# Adorkable_Base_V2_EXP_V1_1.net
KiCad netlist of a schematic drawn in EasyEDA Pro
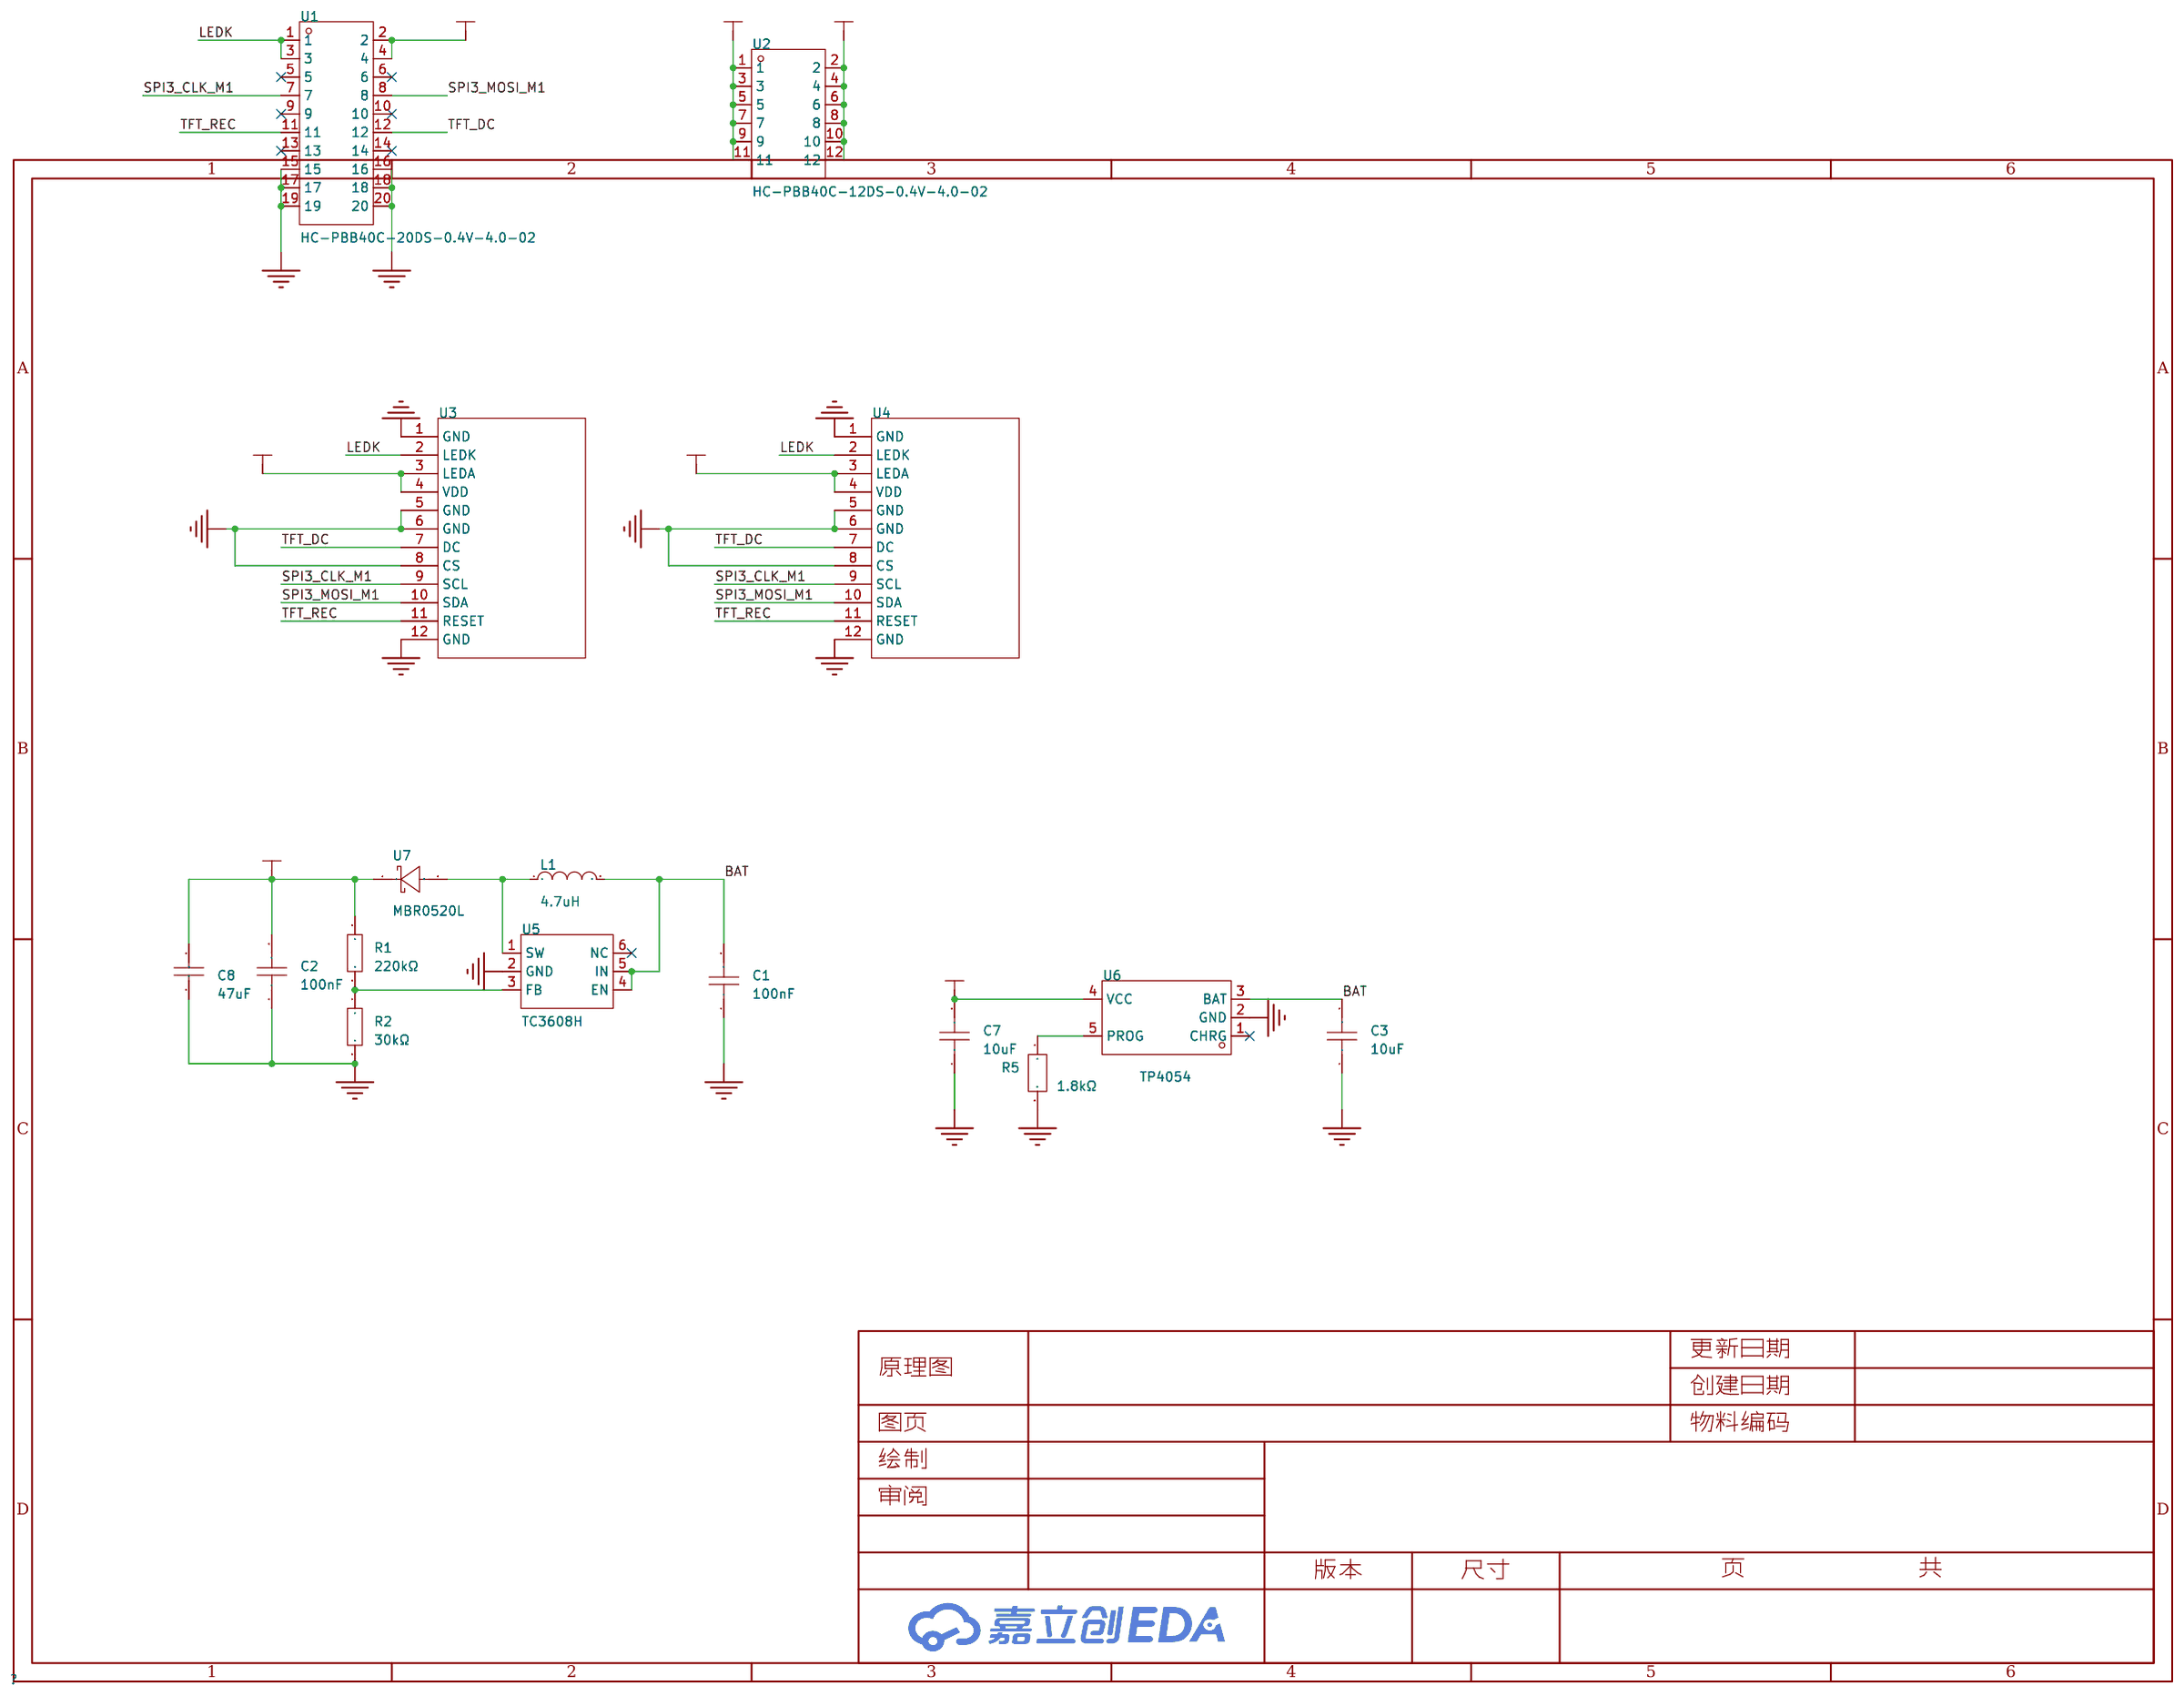
[diagram p0: schematic sheet]

(export (version "E")
  (design (tool "Eeschema 10.0.6"))
  (components
    (comp (ref "C1")
      (value "100nF")
      (footprint "easyedapro:C0603")
      (description "容值:100nF;精度:±10%;额定电压:50V;温度系数:X7R;")
      (fields
        (field (name "Manufacturer Part") "CL10B104KB8NNNC")
        (field (name "Manufacturer") "SAMSUNG(三星)")
      )
      (libsource (lib "easyedapro") (part "CL10B104KB8NNNC"))
    )
    (comp (ref "C2")
      (value "100nF")
      (footprint "easyedapro:C0603")
      (description "容值:100nF;精度:±10%;额定电压:50V;温度系数:X7R;")
      (fields
        (field (name "Manufacturer Part") "CL10B104KB8NNNC")
        (field (name "Manufacturer") "SAMSUNG(三星)")
      )
      (libsource (lib "easyedapro") (part "CL10B104KB8NNNC"))
    )
    (comp (ref "C3")
      (value "10uF")
      (footprint "easyedapro:C0603")
      (description "容值:10uF;精度:±10%;额定电压:10V;温度系数:X5R;")
      (fields
        (field (name "Manufacturer Part") "CL10A106KP8NNNC")
        (field (name "Manufacturer") "SAMSUNG(三星)")
      )
      (libsource (lib "easyedapro") (part "CL10A106KP8NNNC"))
    )
    (comp (ref "C7")
      (value "10uF")
      (footprint "easyedapro:C0603")
      (description "容值:10uF;精度:±10%;额定电压:10V;温度系数:X5R;")
      (fields
        (field (name "Manufacturer Part") "CL10A106KP8NNNC")
        (field (name "Manufacturer") "SAMSUNG(三星)")
      )
      (libsource (lib "easyedapro") (part "CL10A106KP8NNNC"))
    )
    (comp (ref "C8")
      (value "47uF")
      (footprint "easyedapro:C0603")
      (description "容值:47uF;精度:±20%;额定电压:6.3V;材质(温度系数):X5R;")
      (fields
        (field (name "Manufacturer Part") "GRM188R60J476ME15D")
        (field (name "Manufacturer") "muRata(村田)")
      )
      (libsource (lib "easyedapro") (part "GRM188R60J476ME15D"))
    )
    (comp (ref "L1")
      (value "4.7uH")
      (footprint "easyedapro:IND-SMD_L2.5-W2.0-VLS252012CX-150M")
      (description "电感值:4.7uH;精度:±20%;额定电流:2A;饱和电流(Isat):2.6A;类型:一体成型电感;")
      (fields
        (field (name "Manufacturer Part") "FTC252010S4R7MBCA")
        (field (name "Manufacturer") "cjiang(长江微电)")
      )
      (libsource (lib "easyedapro") (part "FTC252010S4R7MBCA"))
    )
    (comp (ref "R1")
      (value "220kΩ")
      (footprint "easyedapro:R0603")
      (description "电阻类型:厚膜电阻;阻值:220kΩ;精度:±1%;功率:100mW;工作电压:75V;温度系数:±100ppm/°C;")
      (fields
        (field (name "Manufacturer Part") "0603WAF2203T5E")
        (field (name "Manufacturer") "UNI-ROYAL(厚声)")
      )
      (libsource (lib "easyedapro") (part "0603WAF2203T5E"))
    )
    (comp (ref "R2")
      (value "30kΩ")
      (footprint "easyedapro:R0603")
      (description "电阻类型:厚膜电阻;阻值:30kΩ;精度:±1%;功率:100mW;工作电压:75V;温度系数:±100ppm/°C;")
      (fields
        (field (name "Manufacturer Part") "0603WAF3002T5E")
        (field (name "Manufacturer") "UNI-ROYAL(厚声)")
      )
      (libsource (lib "easyedapro") (part "0603WAF3002T5E"))
    )
    (comp (ref "R5")
      (value "1.8kΩ")
      (footprint "easyedapro:R0603")
      (description "电阻类型:厚膜电阻;阻值:1.8kΩ;精度:±1%;功率:100mW;工作电压:75V;温度系数:±100ppm/°C;")
      (fields (field (name "Manufacturer Part") "FRC0603F1801TS") (field (name "Manufacturer") "FOJAN(富捷)"))
      (libsource (lib "easyedapro") (part "FRC0603F1801TS"))
    )
    (comp (ref "U1")
      (value "HC-PBB40C-20DS-0.4V-4.0-02")
      (footprint "easyedapro:CONN-SMD_20P-P0.40_DF40C-20DS-0.4V")
      (description "PIN总数:20P;间距:0.4mm;安装方式:立贴;排数:2;额定电流:300mA;工作温度:-40°C~+85°C;")
      (fields (field (name "Manufacturer") "HCTL(华灿天禄)"))
      (libsource (lib "easyedapro") (part "HC-PBB40C-20DS-0.4V-4.0-02"))
    )
    (comp (ref "U2")
      (value "HC-PBB40C-12DS-0.4V-4.0-02")
      (footprint "easyedapro:CONN-SMD_12P-P0.40_HC-PBB40C-12DS-0.4V")
      (description "PIN总数:12P;间距:0.4mm;安装方式:立贴;排数:2;额定电流:300mA;工作温度:-40°C~+85°C;")
      (fields (field (name "Manufacturer") "HCTL(华灿天禄)"))
      (libsource (lib "easyedapro") (part "HC-PBB40C-12DS-0.4V-4.0-02"))
    )
    (comp (ref "U3") (value "~") (footprint "easyedapro:LCD") (libsource (lib "easyedapro") (part "LCD")))
    (comp (ref "U4") (value "~") (footprint "easyedapro:LCD") (libsource (lib "easyedapro") (part "LCD")))
    (comp (ref "U5")
      (value "TC3608H")
      (footprint "easyedapro:SOT-23-6_L2.9-W1.6-P0.95-LS2.8-BR")
      (description "功能类型:升压型;输出类型:-;工作电压:2.3V~15V;输出电压:-;输出电流:-;")
      (fields (field (name "Manufacturer") "FM(富满)"))
      (libsource (lib "easyedapro") (part "TC3608H."))
    )
    (comp (ref "U6")
      (value "TP4054")
      (footprint "easyedapro:TSOT-23-5_L2.9-W1.6-P0.95-LS2.8-BR")
      (description "电源电压:6.5V;最大充电电流:500mA;电池类型:锂离子/聚合物;电池节数:1;")
      (fields (field (name "Manufacturer") "UMW(友台半导体)"))
      (libsource (lib "easyedapro") (part "TP4054_C668215"))
    )
    (comp (ref "U7")
      (value "MBR0520L")
      (footprint "easyedapro:SOD-123_L2.7-W1.6-LS3.7-RD-1")
      (description "二极管配置:独立式;正向压降(Vf):385mV@500mA;直流反向耐压(Vr):20V;整流电流:500mA;")
      (fields (field (name "Manufacturer") "FUXINSEMI(富芯森美)"))
      (libsource (lib "easyedapro") (part "MBR0520L_C5563735"))
    )
  )
  (nets
    (net (code "1") (name "/BAT") (class "Default")
      (node (ref "C1") (pin "2") (pinfunction "2_2") (pintype "unspecified"))
      (node (ref "C3") (pin "2") (pinfunction "2_2") (pintype "unspecified"))
      (node (ref "L1") (pin "2") (pinfunction "2_2") (pintype "unspecified"))
      (node (ref "U5") (pin "4") (pinfunction "EN_4") (pintype "unspecified"))
      (node (ref "U5") (pin "5") (pinfunction "IN_5") (pintype "unspecified"))
      (node (ref "U6") (pin "3") (pinfunction "BAT_3") (pintype "unspecified"))
    )
    (net (code "2") (name "/LEDK") (class "Default")
      (node (ref "U1") (pin "1") (pinfunction "1_1") (pintype "unspecified"))
      (node (ref "U1") (pin "3") (pinfunction "3_3") (pintype "unspecified"))
      (node (ref "U3") (pin "2") (pinfunction "LEDK_2") (pintype "input"))
      (node (ref "U4") (pin "2") (pinfunction "LEDK_2") (pintype "input"))
    )
    (net (code "3") (name "/SPI3_CLK_M1") (class "Default")
      (node (ref "U1") (pin "7") (pinfunction "7_7") (pintype "unspecified"))
      (node (ref "U3") (pin "9") (pinfunction "SCL_9") (pintype "input"))
      (node (ref "U4") (pin "9") (pinfunction "SCL_9") (pintype "input"))
    )
    (net (code "4") (name "/SPI3_MOSI_M1") (class "Default")
      (node (ref "U1") (pin "8") (pinfunction "8_8") (pintype "unspecified"))
      (node (ref "U3") (pin "10") (pinfunction "SDA_10") (pintype "input"))
      (node (ref "U4") (pin "10") (pinfunction "SDA_10") (pintype "input"))
    )
    (net (code "5") (name "/TFT_DC") (class "Default")
      (node (ref "U1") (pin "12") (pinfunction "12_12") (pintype "unspecified"))
      (node (ref "U3") (pin "7") (pinfunction "DC_7") (pintype "input"))
      (node (ref "U4") (pin "7") (pinfunction "DC_7") (pintype "input"))
    )
    (net (code "6") (name "/TFT_REC") (class "Default")
      (node (ref "U1") (pin "11") (pinfunction "11_11") (pintype "unspecified"))
      (node (ref "U3") (pin "11") (pinfunction "RESET_11") (pintype "input"))
      (node (ref "U4") (pin "11") (pinfunction "RESET_11") (pintype "input"))
    )
    (net (code "7") (name "GND") (class "Default")
      (node (ref "C1") (pin "1") (pinfunction "1_1") (pintype "unspecified"))
      (node (ref "C2") (pin "1") (pinfunction "1_1") (pintype "unspecified"))
      (node (ref "C3") (pin "1") (pinfunction "1_1") (pintype "unspecified"))
      (node (ref "C7") (pin "1") (pinfunction "1_1") (pintype "unspecified"))
      (node (ref "C8") (pin "1") (pinfunction "1_1") (pintype "input"))
      (node (ref "R2") (pin "2") (pinfunction "2_2") (pintype "input"))
      (node (ref "R5") (pin "2") (pinfunction "2_2") (pintype "unspecified"))
      (node (ref "U1") (pin "15") (pinfunction "15_15") (pintype "unspecified"))
      (node (ref "U1") (pin "16") (pinfunction "16_16") (pintype "unspecified"))
      (node (ref "U1") (pin "17") (pinfunction "17_17") (pintype "unspecified"))
      (node (ref "U1") (pin "18") (pinfunction "18_18") (pintype "unspecified"))
      (node (ref "U1") (pin "19") (pinfunction "19_19") (pintype "unspecified"))
      (node (ref "U1") (pin "20") (pinfunction "20_20") (pintype "unspecified"))
      (node (ref "U3") (pin "1") (pinfunction "GND_1") (pintype "input"))
      (node (ref "U3") (pin "12") (pinfunction "GND_12") (pintype "input"))
      (node (ref "U3") (pin "5") (pinfunction "GND_5") (pintype "input"))
      (node (ref "U3") (pin "6") (pinfunction "GND_6") (pintype "input"))
      (node (ref "U3") (pin "8") (pinfunction "CS_8") (pintype "input"))
      (node (ref "U4") (pin "1") (pinfunction "GND_1") (pintype "input"))
      (node (ref "U4") (pin "12") (pinfunction "GND_12") (pintype "input"))
      (node (ref "U4") (pin "5") (pinfunction "GND_5") (pintype "input"))
      (node (ref "U4") (pin "6") (pinfunction "GND_6") (pintype "input"))
      (node (ref "U4") (pin "8") (pinfunction "CS_8") (pintype "input"))
      (node (ref "U5") (pin "2") (pinfunction "GND_2") (pintype "unspecified"))
      (node (ref "U6") (pin "2") (pinfunction "GND_2") (pintype "unspecified"))
    )
    (net (code "8") (name "Net-(U5-FB)") (class "Default")
      (node (ref "R1") (pin "2") (pinfunction "2_2") (pintype "input"))
      (node (ref "R2") (pin "1") (pinfunction "1_1") (pintype "input"))
      (node (ref "U5") (pin "3") (pinfunction "FB_3") (pintype "unspecified"))
    )
    (net (code "9") (name "Net-(U5-SW)") (class "Default")
      (node (ref "L1") (pin "1") (pinfunction "1_1") (pintype "unspecified"))
      (node (ref "U5") (pin "1") (pinfunction "SW_1") (pintype "unspecified"))
      (node (ref "U7") (pin "2") (pinfunction "2_2") (pintype "unspecified"))
    )
    (net (code "10") (name "Net-(U6-PROG)") (class "Default")
      (node (ref "R5") (pin "1") (pinfunction "1_1") (pintype "unspecified"))
      (node (ref "U6") (pin "5") (pinfunction "PROG_5") (pintype "unspecified"))
    )
    (net (code "11") (name "VCC_3V3") (class "Default")
      (node (ref "U1") (pin "2") (pinfunction "2_2") (pintype "unspecified"))
      (node (ref "U1") (pin "4") (pinfunction "4_4") (pintype "unspecified"))
      (node (ref "U3") (pin "3") (pinfunction "LEDA_3") (pintype "input"))
      (node (ref "U3") (pin "4") (pinfunction "VDD_4") (pintype "input"))
      (node (ref "U4") (pin "3") (pinfunction "LEDA_3") (pintype "input"))
      (node (ref "U4") (pin "4") (pinfunction "VDD_4") (pintype "input"))
    )
    (net (code "12") (name "VCC_5V") (class "Default")
      (node (ref "C7") (pin "2") (pinfunction "2_2") (pintype "unspecified"))
      (node (ref "U2") (pin "1") (pinfunction "1_1") (pintype "unspecified"))
      (node (ref "U2") (pin "11") (pinfunction "11_11") (pintype "unspecified"))
      (node (ref "U2") (pin "3") (pinfunction "3_3") (pintype "unspecified"))
      (node (ref "U2") (pin "5") (pinfunction "5_5") (pintype "unspecified"))
      (node (ref "U2") (pin "7") (pinfunction "7_7") (pintype "unspecified"))
      (node (ref "U2") (pin "9") (pinfunction "9_9") (pintype "unspecified"))
      (node (ref "U6") (pin "4") (pinfunction "VCC_4") (pintype "unspecified"))
    )
    (net (code "13") (name "VCC_OUT") (class "Default")
      (node (ref "C2") (pin "2") (pinfunction "2_2") (pintype "unspecified"))
      (node (ref "C8") (pin "2") (pinfunction "2_2") (pintype "input"))
      (node (ref "R1") (pin "1") (pinfunction "1_1") (pintype "input"))
      (node (ref "U2") (pin "10") (pinfunction "10_10") (pintype "unspecified"))
      (node (ref "U2") (pin "12") (pinfunction "12_12") (pintype "unspecified"))
      (node (ref "U2") (pin "2") (pinfunction "2_2") (pintype "unspecified"))
      (node (ref "U2") (pin "4") (pinfunction "4_4") (pintype "unspecified"))
      (node (ref "U2") (pin "6") (pinfunction "6_6") (pintype "unspecified"))
      (node (ref "U2") (pin "8") (pinfunction "8_8") (pintype "unspecified"))
      (node (ref "U7") (pin "1") (pinfunction "1_1") (pintype "unspecified"))
    )
    (net (code "14") (name "unconnected-(U1-Pad5)") (class "Default")
      (node (ref "U1") (pin "5") (pinfunction "5_5") (pintype "unspecified+no_connect"))
    )
    (net (code "15") (name "unconnected-(U1-Pad6)") (class "Default")
      (node (ref "U1") (pin "6") (pinfunction "6_6") (pintype "unspecified+no_connect"))
    )
    (net (code "16") (name "unconnected-(U1-Pad9)") (class "Default")
      (node (ref "U1") (pin "9") (pinfunction "9_9") (pintype "unspecified+no_connect"))
    )
    (net (code "17") (name "unconnected-(U1-Pad10)") (class "Default")
      (node (ref "U1") (pin "10") (pinfunction "10_10") (pintype "unspecified+no_connect"))
    )
    (net (code "18") (name "unconnected-(U1-Pad13)") (class "Default")
      (node (ref "U1") (pin "13") (pinfunction "13_13") (pintype "unspecified+no_connect"))
    )
    (net (code "19") (name "unconnected-(U1-Pad14)") (class "Default")
      (node (ref "U1") (pin "14") (pinfunction "14_14") (pintype "unspecified+no_connect"))
    )
    (net (code "20") (name "unconnected-(U5-NC-Pad6)") (class "Default")
      (node (ref "U5") (pin "6") (pinfunction "NC_6") (pintype "unspecified+no_connect"))
    )
    (net (code "21") (name "unconnected-(U6-CHRG-Pad1)") (class "Default")
      (node (ref "U6") (pin "1") (pinfunction "CHRG_1") (pintype "unspecified+no_connect"))
    )
  )
)
